# ExternalConnections.net
KiCad netlist of a schematic drawn in Altium Designer
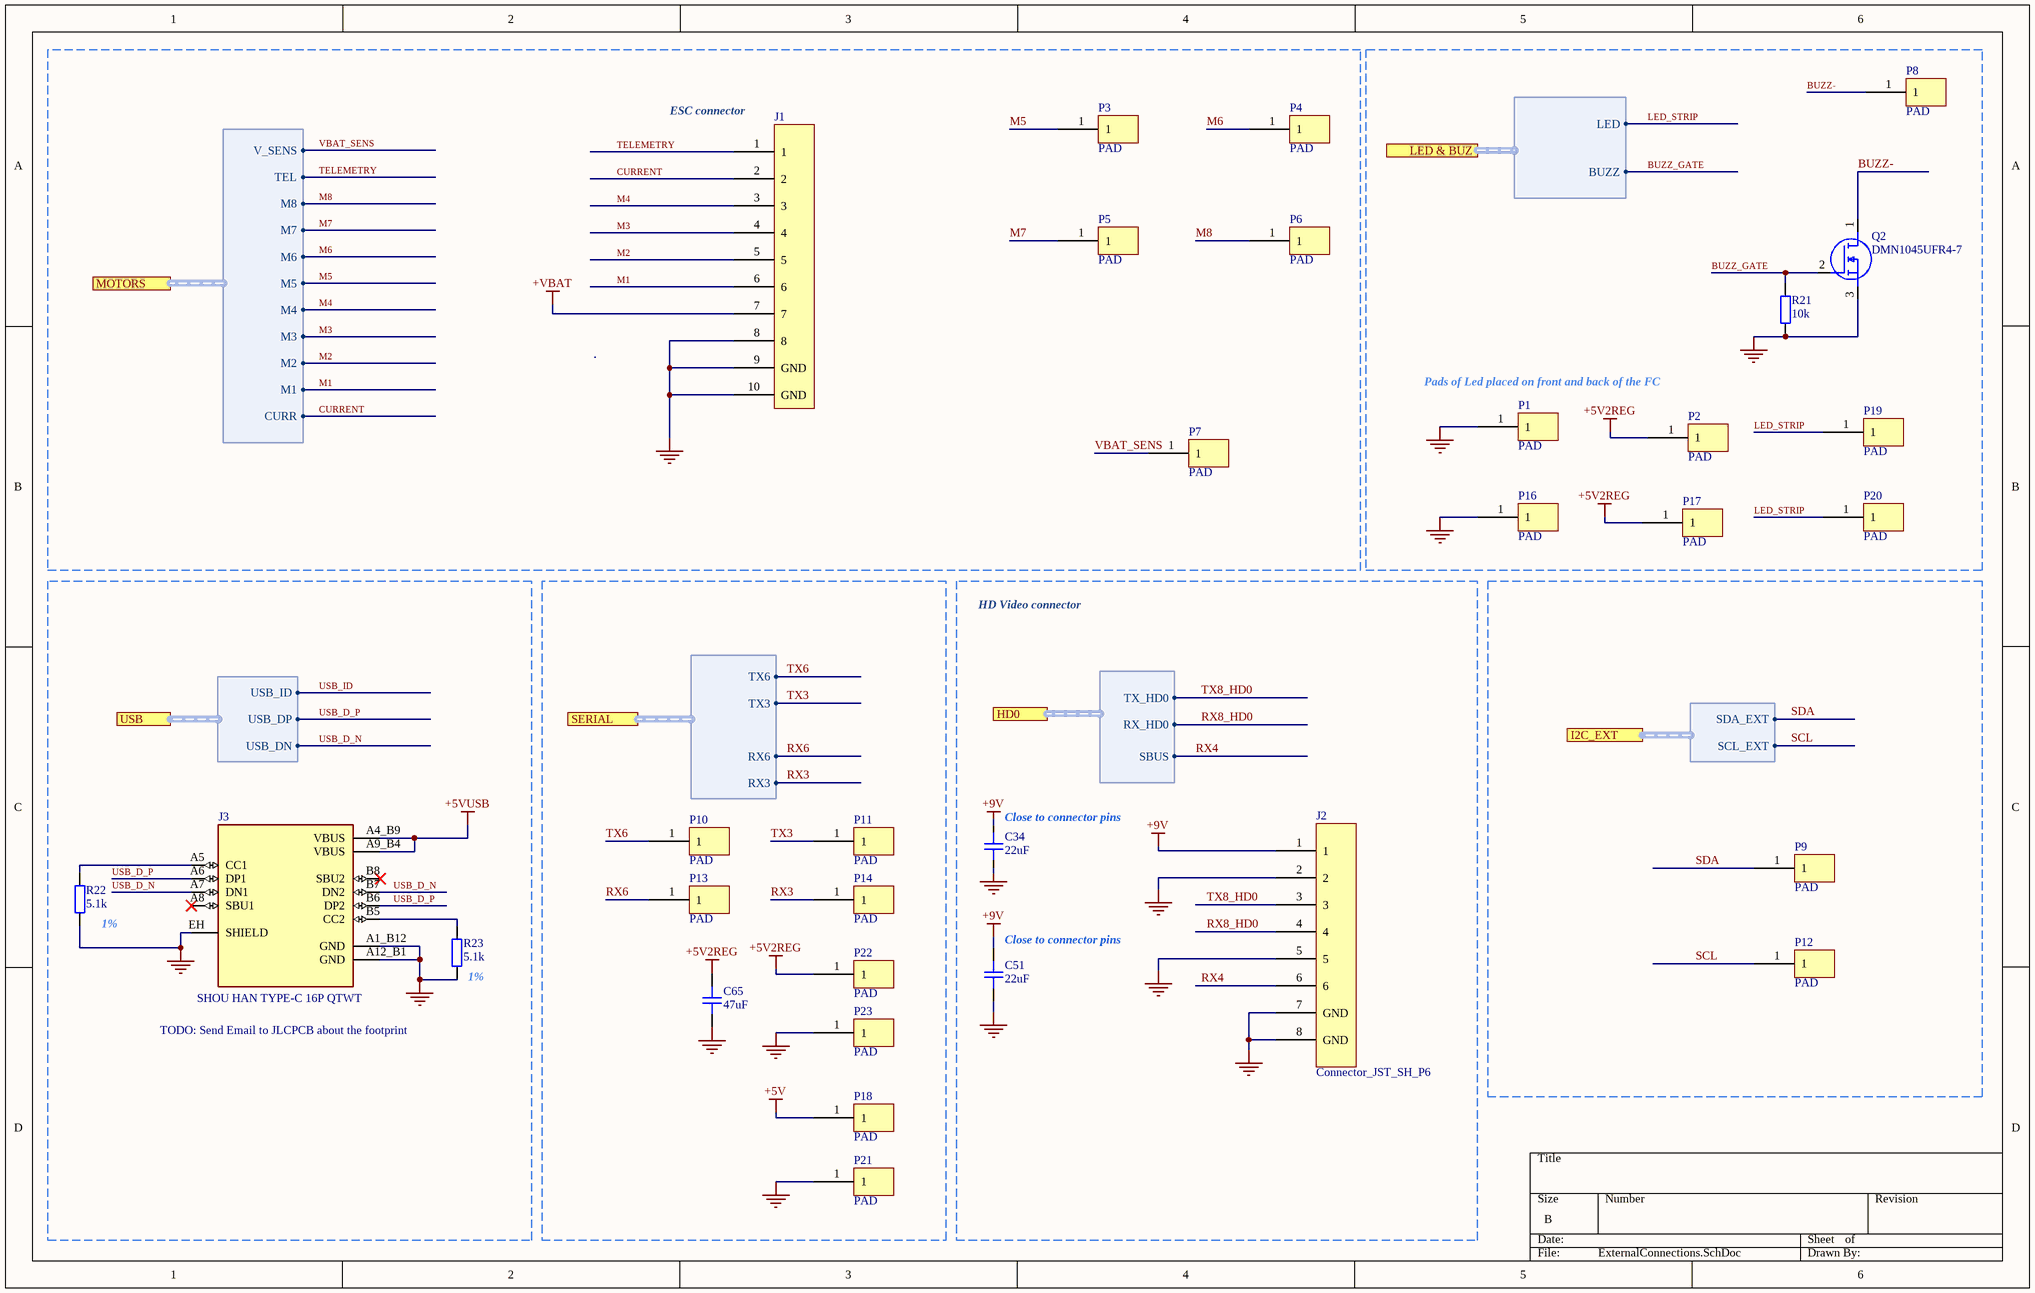
[diagram p0: ExternalConnections.SchDoc]

(export (version "E")
  (design (tool "Eeschema 10.0.6"))
  (components
    (comp (ref "C34")
      (value "22uF")
      (footprint "CAP_0603")
      (description "Capacitor SMD 0603")
      (libsource (lib "Schematic-Lib-PhilsLab") (part "CAP_0603"))
    )
    (comp (ref "C51")
      (value "22uF")
      (footprint "CAP_0603")
      (description "Capacitor SMD 0603")
      (libsource (lib "Schematic-Lib-PhilsLab") (part "CAP_0603"))
    )
    (comp (ref "C65")
      (value "47uF")
      (footprint "CAP_0603")
      (description "Capacitor SMD 0603")
      (libsource (lib "Schematic-Lib-PhilsLab") (part "CAP_0603"))
    )
    (comp (ref "J1")
      (value "Connector_JST_SH_P8")
      (footprint "Connector_JST_SH_P8")
      (fields (field (name "LCSC PART #") "C3041142"))
      (libsource (lib "Schematic-Lib-Singu") (part "Connector_JST_SH_P8"))
    )
    (comp (ref "J2")
      (value "Connector_JST_SH_P6")
      (footprint "Connector_JST_SH_P6")
      (fields (field (name "LCSC PART #") "C3041141"))
      (libsource (lib "Schematic-Lib-Singu") (part "Connector_JST_SH_P6"))
    )
    (comp (ref "J3")
      (value "SHOU HAN TYPE-C 16P QTWT")
      (footprint "USBC_NoHolse")
      (fields
        (field (name "LCSC PART #") "C5187472")
        (field (name "MFR. PART #") "TYPE-C 16P QTWT")
        (field (name "MANUFACTURER") "SHOU HAN")
      )
      (libsource (lib "Schematic-Lib-Singu") (part "SHOU HAN TYPE-C 16P QTWT"))
    )
    (comp (ref "P1") (value "PAD") (footprint "PAD") (libsource (lib "Schematic-Lib-Singu") (part "PAD")))
    (comp (ref "P2") (value "PAD") (footprint "PAD") (libsource (lib "Schematic-Lib-Singu") (part "PAD")))
    (comp (ref "P3") (value "PAD") (footprint "PAD") (libsource (lib "Schematic-Lib-Singu") (part "PAD")))
    (comp (ref "P4") (value "PAD") (footprint "PAD") (libsource (lib "Schematic-Lib-Singu") (part "PAD")))
    (comp (ref "P5") (value "PAD") (footprint "PAD") (libsource (lib "Schematic-Lib-Singu") (part "PAD")))
    (comp (ref "P6") (value "PAD") (footprint "PAD") (libsource (lib "Schematic-Lib-Singu") (part "PAD")))
    (comp (ref "P7") (value "PAD") (footprint "PAD") (libsource (lib "Schematic-Lib-Singu") (part "PAD")))
    (comp (ref "P8") (value "PAD") (footprint "PAD") (libsource (lib "Schematic-Lib-Singu") (part "PAD")))
    (comp (ref "P9") (value "PAD") (footprint "PAD") (libsource (lib "Schematic-Lib-Singu") (part "PAD")))
    (comp (ref "P10") (value "PAD") (footprint "PAD") (libsource (lib "Schematic-Lib-Singu") (part "PAD")))
    (comp (ref "P11") (value "PAD") (footprint "PAD") (libsource (lib "Schematic-Lib-Singu") (part "PAD")))
    (comp (ref "P12") (value "PAD") (footprint "PAD") (libsource (lib "Schematic-Lib-Singu") (part "PAD")))
    (comp (ref "P13") (value "PAD") (footprint "PAD") (libsource (lib "Schematic-Lib-Singu") (part "PAD")))
    (comp (ref "P14") (value "PAD") (footprint "PAD") (libsource (lib "Schematic-Lib-Singu") (part "PAD")))
    (comp (ref "P16") (value "PAD") (footprint "PAD") (libsource (lib "Schematic-Lib-Singu") (part "PAD")))
    (comp (ref "P17") (value "PAD") (footprint "PAD") (libsource (lib "Schematic-Lib-Singu") (part "PAD")))
    (comp (ref "P18") (value "PAD") (footprint "PAD") (libsource (lib "Schematic-Lib-Singu") (part "PAD")))
    (comp (ref "P19") (value "PAD") (footprint "PAD") (libsource (lib "Schematic-Lib-Singu") (part "PAD")))
    (comp (ref "P20") (value "PAD") (footprint "PAD") (libsource (lib "Schematic-Lib-Singu") (part "PAD")))
    (comp (ref "P21") (value "PAD") (footprint "PAD") (libsource (lib "Schematic-Lib-Singu") (part "PAD")))
    (comp (ref "P22") (value "PAD") (footprint "PAD") (libsource (lib "Schematic-Lib-Singu") (part "PAD")))
    (comp (ref "P23") (value "PAD") (footprint "PAD") (libsource (lib "Schematic-Lib-Singu") (part "PAD")))
    (comp (ref "Q2")
      (value "DMN1045UFR4-7")
      (footprint "Footprint-Lib-Singu:DMP1200UFR47")
      (description "MOSFET (N-Channel)")
      (fields (field (name "MOUSER PART NUMBER") "621-DMN1045UFR4-7"))
      (libsource (lib "Schematic-Lib-Singu") (part "DMN1045UFR4-7"))
    )
    (comp (ref "R21")
      (value "10k")
      (footprint "RES_0201")
      (description "Resistor SMD 0201")
      (libsource (lib "Schematic-Lib-PhilsLab") (part "RES_0201"))
    )
    (comp (ref "R22")
      (value "5.1k")
      (footprint "RES_0201")
      (description "Resistor SMD 0201")
      (libsource (lib "Schematic-Lib-PhilsLab") (part "RES_0201"))
    )
    (comp (ref "R23")
      (value "5.1k")
      (footprint "RES_0201")
      (description "Resistor SMD 0201")
      (libsource (lib "Schematic-Lib-PhilsLab") (part "RES_0201"))
    )
  )
  (nets
    (net (code "7") (name "+5V") (class "Default")
      (node (ref "P18") (pin "1") (pinfunction "1_1") (pintype "passive"))
    )
    (net (code "8") (name "+5V2REG") (class "Default")
      (node (ref "C65") (pin "1") (pinfunction "1_1") (pintype "passive"))
      (node (ref "P17") (pin "1") (pinfunction "1_1") (pintype "passive"))
      (node (ref "P2") (pin "1") (pinfunction "1_1") (pintype "passive"))
      (node (ref "P22") (pin "1") (pinfunction "1_1") (pintype "passive"))
    )
    (net (code "9") (name "+5VUSB") (class "Default")
      (node (ref "J3") (pin "A4_B9") (pinfunction "VBUS_A4_B9") (pintype "power_in"))
      (node (ref "J3") (pin "A9_B4") (pinfunction "VBUS_A9_B4") (pintype "power_in"))
    )
    (net (code "10") (name "+9V") (class "Default")
      (node (ref "C34") (pin "1") (pinfunction "1_1") (pintype "passive"))
      (node (ref "C51") (pin "1") (pinfunction "1_1") (pintype "passive"))
      (node (ref "J2") (pin "1") (pinfunction "1_1") (pintype "passive"))
    )
    (net (code "11") (name "+VBAT") (class "Default")
      (node (ref "J1") (pin "7") (pinfunction "7_7") (pintype "passive"))
    )
    (net (code "12") (name "/BUZZ-") (class "Default")
      (node (ref "P8") (pin "1") (pinfunction "1_1") (pintype "passive"))
      (node (ref "Q2") (pin "1") (pinfunction "D_1") (pintype "passive"))
    )
    (net (code "13") (name "/BUZZ_GATE") (class "Default")
      (node (ref "Q2") (pin "2") (pinfunction "G_2") (pintype "passive"))
      (node (ref "R21") (pin "2") (pinfunction "2_2") (pintype "passive"))
    )
    (net (code "14") (name "/CURRENT") (class "Default")
      (node (ref "J1") (pin "2") (pinfunction "2_2") (pintype "passive"))
    )
    (net (code "15") (name "/LED_STRIP") (class "Default")
      (node (ref "P19") (pin "1") (pinfunction "1_1") (pintype "passive"))
      (node (ref "P20") (pin "1") (pinfunction "1_1") (pintype "passive"))
    )
    (net (code "16") (name "/M1") (class "Default")
      (node (ref "J1") (pin "6") (pinfunction "6_6") (pintype "passive"))
    )
    (net (code "17") (name "/M2") (class "Default")
      (node (ref "J1") (pin "5") (pinfunction "5_5") (pintype "passive"))
    )
    (net (code "18") (name "/M3") (class "Default")
      (node (ref "J1") (pin "4") (pinfunction "4_4") (pintype "passive"))
    )
    (net (code "19") (name "/M4") (class "Default")
      (node (ref "J1") (pin "3") (pinfunction "3_3") (pintype "passive"))
    )
    (net (code "20") (name "/M5") (class "Default")
      (node (ref "P3") (pin "1") (pinfunction "1_1") (pintype "passive"))
    )
    (net (code "21") (name "/M6") (class "Default")
      (node (ref "P4") (pin "1") (pinfunction "1_1") (pintype "passive"))
    )
    (net (code "22") (name "/M7") (class "Default")
      (node (ref "P5") (pin "1") (pinfunction "1_1") (pintype "passive"))
    )
    (net (code "23") (name "/M8") (class "Default")
      (node (ref "P6") (pin "1") (pinfunction "1_1") (pintype "passive"))
    )
    (net (code "24") (name "/RX3") (class "Default")
      (node (ref "P14") (pin "1") (pinfunction "1_1") (pintype "passive"))
    )
    (net (code "25") (name "/RX4") (class "Default")
      (node (ref "J2") (pin "6") (pinfunction "6_6") (pintype "passive"))
    )
    (net (code "26") (name "/RX6") (class "Default")
      (node (ref "P13") (pin "1") (pinfunction "1_1") (pintype "passive"))
    )
    (net (code "27") (name "/RX8_HD0") (class "Default")
      (node (ref "J2") (pin "4") (pinfunction "4_4") (pintype "passive"))
    )
    (net (code "28") (name "/SCL") (class "Default")
      (node (ref "P12") (pin "1") (pinfunction "1_1") (pintype "passive"))
    )
    (net (code "29") (name "/SDA") (class "Default")
      (node (ref "P9") (pin "1") (pinfunction "1_1") (pintype "passive"))
    )
    (net (code "30") (name "/TELEMETRY") (class "Default")
      (node (ref "J1") (pin "1") (pinfunction "1_1") (pintype "passive"))
    )
    (net (code "31") (name "/TX3") (class "Default")
      (node (ref "P11") (pin "1") (pinfunction "1_1") (pintype "passive"))
    )
    (net (code "32") (name "/TX6") (class "Default")
      (node (ref "P10") (pin "1") (pinfunction "1_1") (pintype "passive"))
    )
    (net (code "33") (name "/TX8_HD0") (class "Default")
      (node (ref "J2") (pin "3") (pinfunction "3_3") (pintype "passive"))
    )
    (net (code "34") (name "/USB_D_N") (class "Default")
      (node (ref "J3") (pin "A7") (pinfunction "DN1_A7") (pintype "bidirectional"))
      (node (ref "J3") (pin "B7") (pinfunction "DN2_B7") (pintype "bidirectional"))
    )
    (net (code "35") (name "/USB_D_P") (class "Default")
      (node (ref "J3") (pin "A6") (pinfunction "DP1_A6") (pintype "bidirectional"))
      (node (ref "J3") (pin "B6") (pinfunction "DP2_B6") (pintype "bidirectional"))
    )
    (net (code "37") (name "/VBAT_SENS") (class "Default")
      (node (ref "P7") (pin "1") (pinfunction "1_1") (pintype "passive"))
    )
    (net (code "44") (name "GND") (class "Default")
      (node (ref "C34") (pin "2") (pinfunction "2_2") (pintype "passive"))
      (node (ref "C51") (pin "2") (pinfunction "2_2") (pintype "passive"))
      (node (ref "C65") (pin "2") (pinfunction "2_2") (pintype "passive"))
      (node (ref "J1") (pin "10") (pinfunction "GND_10") (pintype "passive"))
      (node (ref "J1") (pin "8") (pinfunction "8_8") (pintype "passive"))
      (node (ref "J1") (pin "9") (pinfunction "GND_9") (pintype "passive"))
      (node (ref "J2") (pin "2") (pinfunction "2_2") (pintype "passive"))
      (node (ref "J2") (pin "5") (pinfunction "5_5") (pintype "passive"))
      (node (ref "J2") (pin "7") (pinfunction "GND_7") (pintype "passive"))
      (node (ref "J2") (pin "8") (pinfunction "GND_8") (pintype "passive"))
      (node (ref "J3") (pin "A12_B1") (pinfunction "GND_A12_B1") (pintype "power_in"))
      (node (ref "J3") (pin "A1_B12") (pinfunction "GND_A1_B12") (pintype "power_in"))
      (node (ref "J3") (pin "EH") (pinfunction "SHIELD_EH") (pintype "passive"))
      (node (ref "P1") (pin "1") (pinfunction "1_1") (pintype "passive"))
      (node (ref "P16") (pin "1") (pinfunction "1_1") (pintype "passive"))
      (node (ref "P21") (pin "1") (pinfunction "1_1") (pintype "passive"))
      (node (ref "P23") (pin "1") (pinfunction "1_1") (pintype "passive"))
      (node (ref "Q2") (pin "3") (pinfunction "S_3") (pintype "passive"))
      (node (ref "R21") (pin "1") (pinfunction "1_1") (pintype "passive"))
      (node (ref "R22") (pin "1") (pinfunction "1_1") (pintype "passive"))
      (node (ref "R23") (pin "1") (pinfunction "1_1") (pintype "passive"))
    )
    (net (code "45") (name "Net-(J3-CC1)") (class "Default")
      (node (ref "J3") (pin "A5") (pinfunction "CC1_A5") (pintype "bidirectional"))
      (node (ref "R22") (pin "2") (pinfunction "2_2") (pintype "passive"))
    )
    (net (code "46") (name "Net-(J3-CC2)") (class "Default")
      (node (ref "J3") (pin "B5") (pinfunction "CC2_B5") (pintype "bidirectional"))
      (node (ref "R23") (pin "2") (pinfunction "2_2") (pintype "passive"))
    )
    (net (code "47") (name "unconnected-(J3-SBU1-PadA8)") (class "Default")
      (node (ref "J3") (pin "A8") (pinfunction "SBU1_A8") (pintype "bidirectional+no_connect"))
    )
    (net (code "48") (name "unconnected-(J3-SBU2-PadB8)") (class "Default")
      (node (ref "J3") (pin "B8") (pinfunction "SBU2_B8") (pintype "bidirectional+no_connect"))
    )
  )
)
